# tempLogger.net
KiCad netlist of a schematic drawn in EAGLE
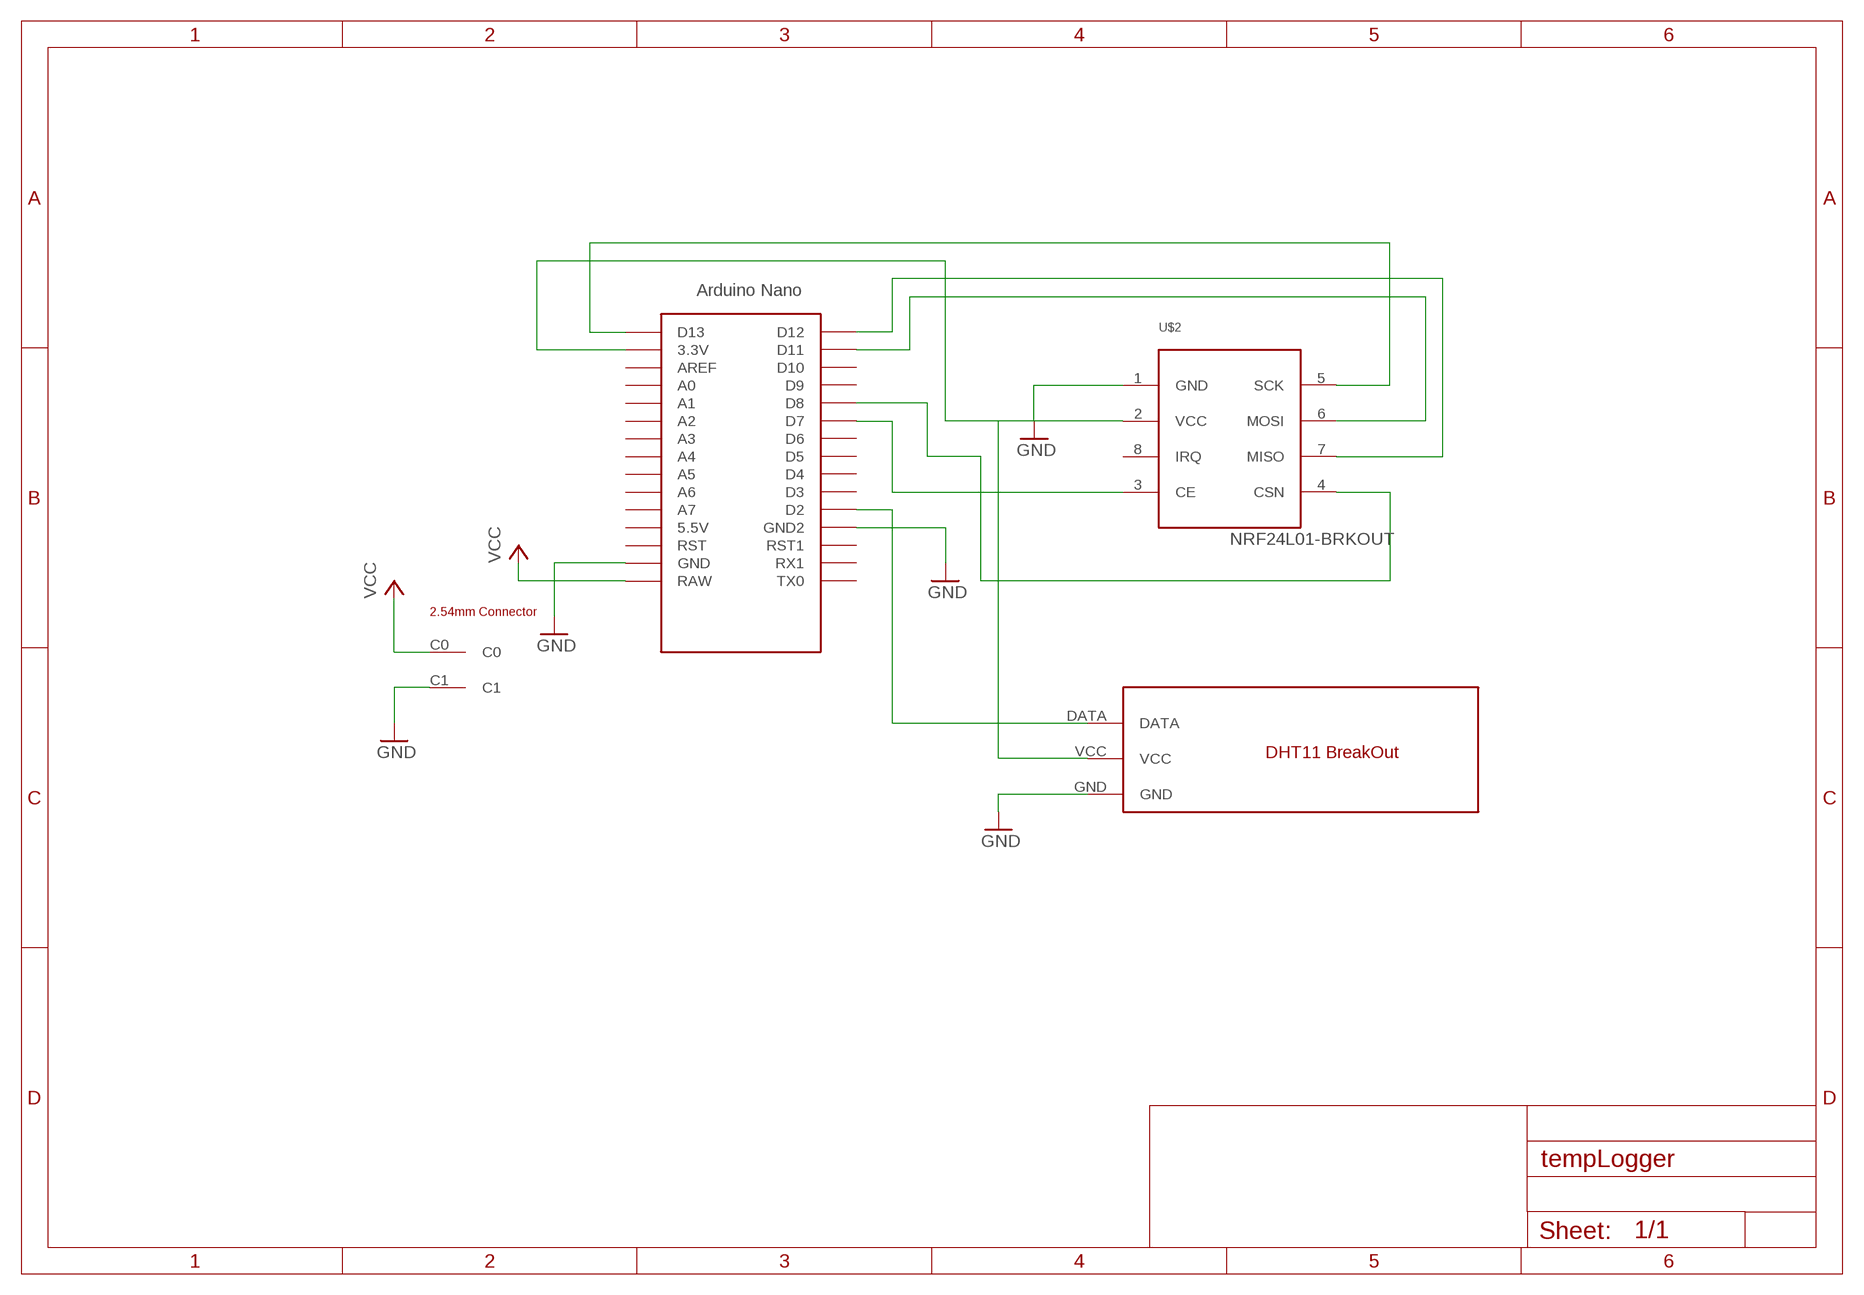
[diagram p0: schematic, sheet 1]

(export (version "E")
  (design (tool "Eeschema 10.0.6"))
  (components
    (comp (ref "U$1")
      (value "NANO")
      (footprint "eagle-import:NANO")
      (libsource (lib "eagle-import") (part "NANO"))
    )
    (comp (ref "U$2")
      (value "NRF24L01-BRKOUT")
      (footprint "eagle-import:NRF24L01-BKKOUT")
      (libsource (lib "eagle-import") (part "NRF24L01-BRKOUT"))
    )
    (comp (ref "U$3")
      (value "DHT11BREAKOUTVERTICAL")
      (footprint "eagle-import:DHT11BREAKOUT_VERTICAL")
      (libsource (lib "eagle-import") (part "DHT11BREAKOUTVERTICAL"))
    )
    (comp (ref "U$4")
      (value "TWO_PINS_CONNECTOR_2_54MM")
      (footprint "eagle-import:TWO_PINS_CONNECTOR_2_54MM")
      (libsource (lib "eagle-import") (part "TWO_PINS_CONNECTOR_2_54MM"))
    )
  )
  (nets
    (net (code "1") (name "GND") (class "Default")
      (node (ref "U$1") (pin "GND") (pinfunction "GND_GND") (pintype "bidirectional"))
      (node (ref "U$1") (pin "GND1") (pinfunction "GND2_GND1") (pintype "bidirectional"))
      (node (ref "U$2") (pin "1") (pinfunction "GND_1") (pintype "bidirectional"))
      (node (ref "U$3") (pin "GND") (pinfunction "GND_GND") (pintype "bidirectional"))
      (node (ref "U$4") (pin "C1") (pinfunction "C1_C1") (pintype "bidirectional"))
    )
    (net (code "2") (name "Net-(U$1-PadD2)") (class "Default")
      (node (ref "U$1") (pin "D2") (pinfunction "D2_D2") (pintype "bidirectional"))
      (node (ref "U$3") (pin "DATA") (pinfunction "DATA_DATA") (pintype "bidirectional"))
    )
    (net (code "3") (name "Net-(U$2-CE)") (class "Default")
      (node (ref "U$1") (pin "D7") (pinfunction "D7_D7") (pintype "bidirectional"))
      (node (ref "U$2") (pin "3") (pinfunction "CE_3") (pintype "bidirectional"))
    )
    (net (code "4") (name "Net-(U$2-CSN)") (class "Default")
      (node (ref "U$1") (pin "D8") (pinfunction "D8_D8") (pintype "bidirectional"))
      (node (ref "U$2") (pin "4") (pinfunction "CSN_4") (pintype "bidirectional"))
    )
    (net (code "5") (name "Net-(U$2-MISO)") (class "Default")
      (node (ref "U$1") (pin "D12") (pinfunction "D12_D12") (pintype "bidirectional"))
      (node (ref "U$2") (pin "7") (pinfunction "MISO_7") (pintype "bidirectional"))
    )
    (net (code "6") (name "Net-(U$2-MOSI)") (class "Default")
      (node (ref "U$1") (pin "D11") (pinfunction "D11_D11") (pintype "bidirectional"))
      (node (ref "U$2") (pin "6") (pinfunction "MOSI_6") (pintype "bidirectional"))
    )
    (net (code "7") (name "Net-(U$2-SCK)") (class "Default")
      (node (ref "U$1") (pin "D13") (pinfunction "D13_D13") (pintype "bidirectional"))
      (node (ref "U$2") (pin "5") (pinfunction "SCK_5") (pintype "bidirectional"))
    )
    (net (code "8") (name "Net-(U$2-VCC)") (class "Default")
      (node (ref "U$1") (pin "3.3V") (pinfunction "3.3V_3.3V") (pintype "bidirectional"))
      (node (ref "U$2") (pin "2") (pinfunction "VCC_2") (pintype "bidirectional"))
      (node (ref "U$3") (pin "VCC") (pinfunction "VCC_VCC") (pintype "bidirectional"))
    )
    (net (code "9") (name "VCC") (class "Default")
      (node (ref "U$1") (pin "RAW") (pinfunction "RAW_RAW") (pintype "bidirectional"))
      (node (ref "U$4") (pin "C0") (pinfunction "C0_C0") (pintype "bidirectional"))
    )
    (net (code "10") (name "unconnected-(U$1-5.5V-Pad5V)") (class "Default")
      (node (ref "U$1") (pin "5V") (pinfunction "5.5V_5V") (pintype "bidirectional"))
    )
    (net (code "11") (name "unconnected-(U$1-PadA0)") (class "Default")
      (node (ref "U$1") (pin "A0") (pinfunction "A0_A0") (pintype "bidirectional"))
    )
    (net (code "12") (name "unconnected-(U$1-PadA1)") (class "Default")
      (node (ref "U$1") (pin "A1") (pinfunction "A1_A1") (pintype "bidirectional"))
    )
    (net (code "13") (name "unconnected-(U$1-PadA2)") (class "Default")
      (node (ref "U$1") (pin "A2") (pinfunction "A2_A2") (pintype "bidirectional"))
    )
    (net (code "14") (name "unconnected-(U$1-PadA3)") (class "Default")
      (node (ref "U$1") (pin "A3") (pinfunction "A3_A3") (pintype "bidirectional"))
    )
    (net (code "15") (name "unconnected-(U$1-PadA4)") (class "Default")
      (node (ref "U$1") (pin "A4") (pinfunction "A4_A4") (pintype "bidirectional"))
    )
    (net (code "16") (name "unconnected-(U$1-PadA5)") (class "Default")
      (node (ref "U$1") (pin "A5") (pinfunction "A5_A5") (pintype "bidirectional"))
    )
    (net (code "17") (name "unconnected-(U$1-PadA6)") (class "Default")
      (node (ref "U$1") (pin "A6") (pinfunction "A6_A6") (pintype "bidirectional"))
    )
    (net (code "18") (name "unconnected-(U$1-PadA7)") (class "Default")
      (node (ref "U$1") (pin "A7") (pinfunction "A7_A7") (pintype "bidirectional"))
    )
    (net (code "19") (name "unconnected-(U$1-PadAREF)") (class "Default")
      (node (ref "U$1") (pin "AREF") (pinfunction "AREF_AREF") (pintype "bidirectional"))
    )
    (net (code "20") (name "unconnected-(U$1-PadD3)") (class "Default")
      (node (ref "U$1") (pin "D3") (pinfunction "D3_D3") (pintype "bidirectional"))
    )
    (net (code "21") (name "unconnected-(U$1-PadD4)") (class "Default")
      (node (ref "U$1") (pin "D4") (pinfunction "D4_D4") (pintype "bidirectional"))
    )
    (net (code "22") (name "unconnected-(U$1-PadD5)") (class "Default")
      (node (ref "U$1") (pin "D5") (pinfunction "D5_D5") (pintype "bidirectional"))
    )
    (net (code "23") (name "unconnected-(U$1-PadD6)") (class "Default")
      (node (ref "U$1") (pin "D6") (pinfunction "D6_D6") (pintype "bidirectional"))
    )
    (net (code "24") (name "unconnected-(U$1-PadD9)") (class "Default")
      (node (ref "U$1") (pin "D9") (pinfunction "D9_D9") (pintype "bidirectional"))
    )
    (net (code "25") (name "unconnected-(U$1-PadD10)") (class "Default")
      (node (ref "U$1") (pin "D10") (pinfunction "D10_D10") (pintype "bidirectional"))
    )
    (net (code "26") (name "unconnected-(U$1-PadICSP1)") (class "Default")
      (node (ref "U$1") (pin "ICSP1") (pinfunction "ICSP1_ICSP1") (pintype "bidirectional"))
    )
    (net (code "27") (name "unconnected-(U$1-PadICSP2)") (class "Default")
      (node (ref "U$1") (pin "ICSP2") (pinfunction "ICSP2_ICSP2") (pintype "bidirectional"))
    )
    (net (code "28") (name "unconnected-(U$1-PadICSP3)") (class "Default")
      (node (ref "U$1") (pin "ICSP3") (pinfunction "ICSP3_ICSP3") (pintype "bidirectional"))
    )
    (net (code "29") (name "unconnected-(U$1-PadICSP4)") (class "Default")
      (node (ref "U$1") (pin "ICSP4") (pinfunction "ICSP4_ICSP4") (pintype "bidirectional"))
    )
    (net (code "30") (name "unconnected-(U$1-PadICSP5)") (class "Default")
      (node (ref "U$1") (pin "ICSP5") (pinfunction "ICSP5_ICSP5") (pintype "bidirectional"))
    )
    (net (code "31") (name "unconnected-(U$1-PadICSP6)") (class "Default")
      (node (ref "U$1") (pin "ICSP6") (pinfunction "ICSP6_ICSP6") (pintype "bidirectional"))
    )
    (net (code "32") (name "unconnected-(U$1-PadRST)") (class "Default")
      (node (ref "U$1") (pin "RST") (pinfunction "RST_RST") (pintype "bidirectional"))
    )
    (net (code "33") (name "unconnected-(U$1-PadRST1)") (class "Default")
      (node (ref "U$1") (pin "RST1") (pinfunction "RST1_RST1") (pintype "bidirectional"))
    )
    (net (code "34") (name "unconnected-(U$1-PadRX1)") (class "Default")
      (node (ref "U$1") (pin "RX1") (pinfunction "RX1_RX1") (pintype "bidirectional"))
    )
    (net (code "35") (name "unconnected-(U$1-PadTX0)") (class "Default")
      (node (ref "U$1") (pin "TX0") (pinfunction "TX0_TX0") (pintype "bidirectional"))
    )
    (net (code "36") (name "unconnected-(U$2-IRQ-Pad8)") (class "Default")
      (node (ref "U$2") (pin "8") (pinfunction "IRQ_8") (pintype "bidirectional"))
    )
  )
)
